# Buck-Boost_1.net
KiCad netlist of a schematic drawn in Altium Designer
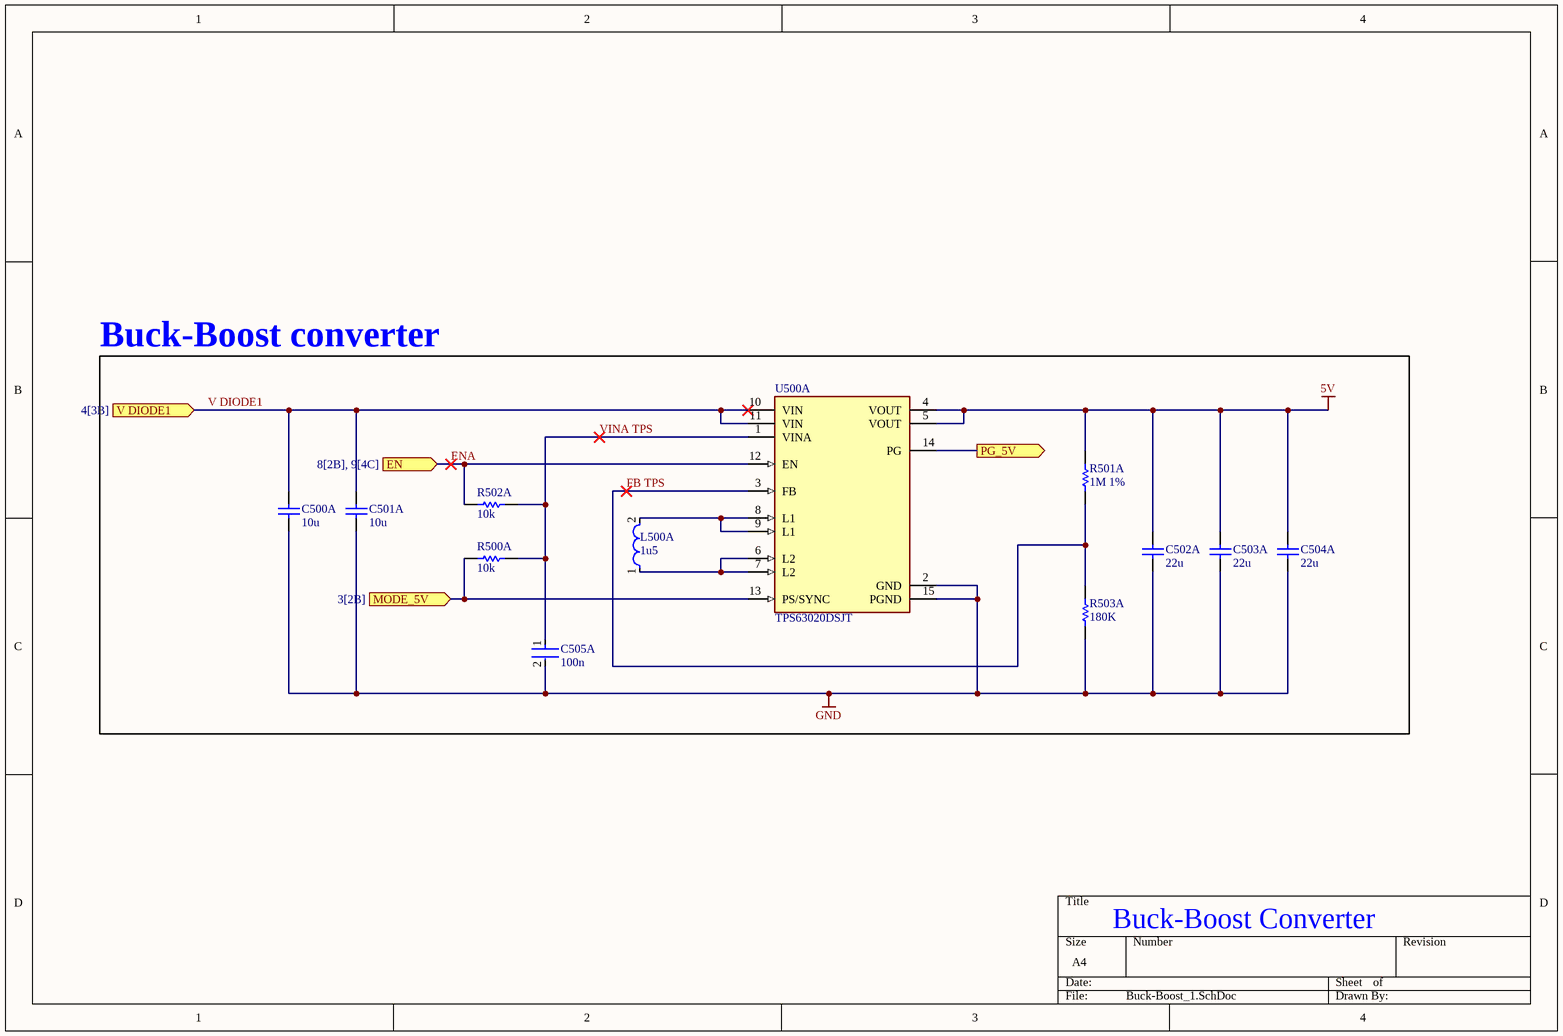
[diagram p0: Buck-Boost_1.SchDoc]

(export (version "E")
  (design (tool "Eeschema 10.0.6"))
  (components
    (comp (ref "C500A")
      (value "10u")
      (footprint "CAPC3216X180X50LL20T25")
      (description "Chip Capacitor, 10 uF, +/- 10%, 10 V, -55 to 125 degC, 1206 (3216 Metric), RoHS, Tape and Reel")
      (fields (field (name "TOLERANCE") "10%") (field (name "MANUFACTURER") "Kemet"))
      (libsource (lib "Altium Content Vault") (part "CAP-NP-2"))
    )
    (comp (ref "C501A")
      (value "10u")
      (footprint "CAPC3216X180X50LL20T25")
      (description "Chip Capacitor, 10 uF, +/- 10%, 10 V, -55 to 125 degC, 1206 (3216 Metric), RoHS, Tape and Reel")
      (fields (field (name "TOLERANCE") "10%") (field (name "MANUFACTURER") "Kemet"))
      (libsource (lib "Altium Content Vault") (part "CAP-NP-2"))
    )
    (comp (ref "C502A")
      (value "22u")
      (footprint "CAPC1206(3216)190_L")
      (description "CAP 22uF 6.3V ±20% 1206 (3216 Metric) Thickness 1.9mm SMD")
      (fields (field (name "TOLERANCE") "Â±20%"))
      (libsource (lib "Altium Content Vault") (part "CAP"))
    )
    (comp (ref "C503A")
      (value "22u")
      (footprint "CAPC1206(3216)190_L")
      (description "CAP 22uF 6.3V ±20% 1206 (3216 Metric) Thickness 1.9mm SMD")
      (fields (field (name "TOLERANCE") "Â±20%"))
      (libsource (lib "Altium Content Vault") (part "CAP"))
    )
    (comp (ref "C504A")
      (value "22u")
      (footprint "CAPC1206(3216)190_L")
      (description "CAP 22uF 6.3V ±20% 1206 (3216 Metric) Thickness 1.9mm SMD")
      (fields (field (name "TOLERANCE") "Â±20%"))
      (libsource (lib "Altium Content Vault") (part "CAP"))
    )
    (comp (ref "C505A")
      (value "100n")
      (footprint "FP-CGA3E-0_3-0_1-IPC_A")
      (description "Cap Ceramic 100nF 50V X7R 10% Pad SMD 0603 +125°C Automotive T/R")
      (fields (field (name "TOLERANCE") "10%") (field (name "VOLTAGE") "50V"))
      (libsource (lib "Altium Content Vault") (part "b4654b650e69147ec39a6b967a45e02"))
    )
    (comp (ref "L500A")
      (value "1u5")
      (footprint "FP-DFE252010C-IPC_A")
      (description "Shielded Wirewound Inductor 1.5uH  2500mA 0.072Ω 1008 (2520)")
      (fields (field (name "TOLERANCE") "20%"))
      (libsource (lib "Altium Content Vault") (part "725321dda6339637d4d059423bc1c3c"))
    )
    (comp (ref "R500A")
      (value "10k")
      (footprint "RESC2013X60X35NL10T20")
      (description "Chip Resistor, 10 KOhm, +/- 1%, 0.125 W, -55 to 155 degC, 0805 (2012 Metric), RoHS, Tape and Reel")
      (fields (field (name "MANUFACTURER") "Yageo"))
      (libsource (lib "Altium Content Vault") (part "RES-2"))
    )
    (comp (ref "R501A")
      (value "1M 1%")
      (footprint "RESC1608X55X25LL10T15")
      (description "Chip Resistor, 1 MOhm, +/- 1%, 100 mW, -55 to 155 degC, 0603 (1608 Metric), RoHS, Tape and Reel")
      (fields (field (name "TOLERANCE") "20%"))
      (libsource (lib "Altium Content Vault") (part "RES-2"))
    )
    (comp (ref "R502A")
      (value "10k")
      (footprint "RESC2013X60X35NL10T20")
      (description "Chip Resistor, 10 KOhm, +/- 1%, 0.125 W, -55 to 155 degC, 0805 (2012 Metric), RoHS, Tape and Reel")
      (fields (field (name "MANUFACTURER") "Yageo"))
      (libsource (lib "Altium Content Vault") (part "RES-2"))
    )
    (comp (ref "R503A")
      (value "180K")
      (footprint "RESC1005X40X25NL05T10")
      (description "Chip Resistor, 180 KOhm, +/- 1%, 62.5 mW, -55 to 155 degC, 0402 (1005 Metric), RoHS, Tape and Reel")
      (fields (field (name "TOLERANCE") "1%") (field (name "MANUFACTURER") "Basic Passives"))
      (libsource (lib "Altium Content Vault") (part "RES-2"))
    )
    (comp (ref "U500A")
      (value "TPS63020DSJT")
      (footprint "FP-DSJ0014A-MFG")
      (description "IC REG BCK BST ADJ 3.5A 14VSON")
      (fields
        (field (name "MANUFACTURER") "Texas Instruments")
        (field (name "OCTOPART") "https://octopart.com/tps63020dsjt-texas+instruments-12976119")
      )
      (libsource (lib "Altium Content Vault") (part "ca84f4b88d1e031d86a58c77b9c066d"))
    )
  )
  (nets
    (net (code "1") (name "/EN") (class "Default")
      (node (ref "R502A") (pin "1") (pinfunction "1_1") (pintype "passive"))
      (node (ref "U500A") (pin "12") (pinfunction "EN_12") (pintype "input"))
    )
    (net (code "4") (name "/FB TPS") (class "Default")
      (node (ref "R501A") (pin "1") (pinfunction "1_1") (pintype "passive"))
      (node (ref "R503A") (pin "2") (pinfunction "2_2") (pintype "passive"))
      (node (ref "U500A") (pin "3") (pinfunction "FB_3") (pintype "input"))
    )
    (net (code "5") (name "/MODE_5V") (class "Default")
      (node (ref "R500A") (pin "1") (pinfunction "1_1") (pintype "passive"))
      (node (ref "U500A") (pin "13") (pinfunction "PS/SYNC_13") (pintype "input"))
    )
    (net (code "6") (name "/PG_5V") (class "Default")
      (node (ref "U500A") (pin "14") (pinfunction "PG_14") (pintype "open_collector"))
    )
    (net (code "8") (name "/V DIODE1") (class "Default")
      (node (ref "C500A") (pin "2") (pinfunction "2_2") (pintype "passive"))
      (node (ref "C501A") (pin "2") (pinfunction "2_2") (pintype "passive"))
      (node (ref "U500A") (pin "10") (pinfunction "VIN_10") (pintype "power_in"))
      (node (ref "U500A") (pin "11") (pinfunction "VIN_11") (pintype "power_in"))
    )
    (net (code "9") (name "/VINA TPS") (class "Default")
      (node (ref "C505A") (pin "1") (pinfunction "1_1") (pintype "passive"))
      (node (ref "R500A") (pin "2") (pinfunction "2_2") (pintype "passive"))
      (node (ref "R502A") (pin "2") (pinfunction "2_2") (pintype "passive"))
      (node (ref "U500A") (pin "1") (pinfunction "VINA_1") (pintype "power_in"))
    )
    (net (code "10") (name "5V") (class "Default")
      (node (ref "C502A") (pin "2") (pinfunction "2_2") (pintype "passive"))
      (node (ref "C503A") (pin "2") (pinfunction "2_2") (pintype "passive"))
      (node (ref "C504A") (pin "2") (pinfunction "2_2") (pintype "passive"))
      (node (ref "R501A") (pin "2") (pinfunction "2_2") (pintype "passive"))
      (node (ref "U500A") (pin "4") (pinfunction "VOUT_4") (pintype "power_in"))
      (node (ref "U500A") (pin "5") (pinfunction "VOUT_5") (pintype "power_in"))
    )
    (net (code "11") (name "GND") (class "Default")
      (node (ref "C500A") (pin "1") (pinfunction "1_1") (pintype "passive"))
      (node (ref "C501A") (pin "1") (pinfunction "1_1") (pintype "passive"))
      (node (ref "C502A") (pin "1") (pinfunction "1_1") (pintype "passive"))
      (node (ref "C503A") (pin "1") (pinfunction "1_1") (pintype "passive"))
      (node (ref "C504A") (pin "1") (pinfunction "1_1") (pintype "passive"))
      (node (ref "C505A") (pin "2") (pinfunction "2_2") (pintype "passive"))
      (node (ref "R503A") (pin "1") (pinfunction "1_1") (pintype "passive"))
      (node (ref "U500A") (pin "15") (pinfunction "PGND_15") (pintype "power_in"))
      (node (ref "U500A") (pin "2") (pinfunction "GND_2") (pintype "power_in"))
    )
    (net (code "12") (name "Net-(L500A-Pad1)") (class "Default")
      (node (ref "L500A") (pin "1") (pinfunction "1_1") (pintype "passive"))
      (node (ref "U500A") (pin "6") (pinfunction "L2_6") (pintype "input"))
      (node (ref "U500A") (pin "7") (pinfunction "L2_7") (pintype "input"))
    )
    (net (code "13") (name "Net-(L500A-Pad2)") (class "Default")
      (node (ref "L500A") (pin "2") (pinfunction "2_2") (pintype "passive"))
      (node (ref "U500A") (pin "8") (pinfunction "L1_8") (pintype "input"))
      (node (ref "U500A") (pin "9") (pinfunction "L1_9") (pintype "input"))
    )
  )
)
